# Varella_Aquisition_Module_-_v_2_0.net
KiCad netlist of a schematic drawn in EAGLE
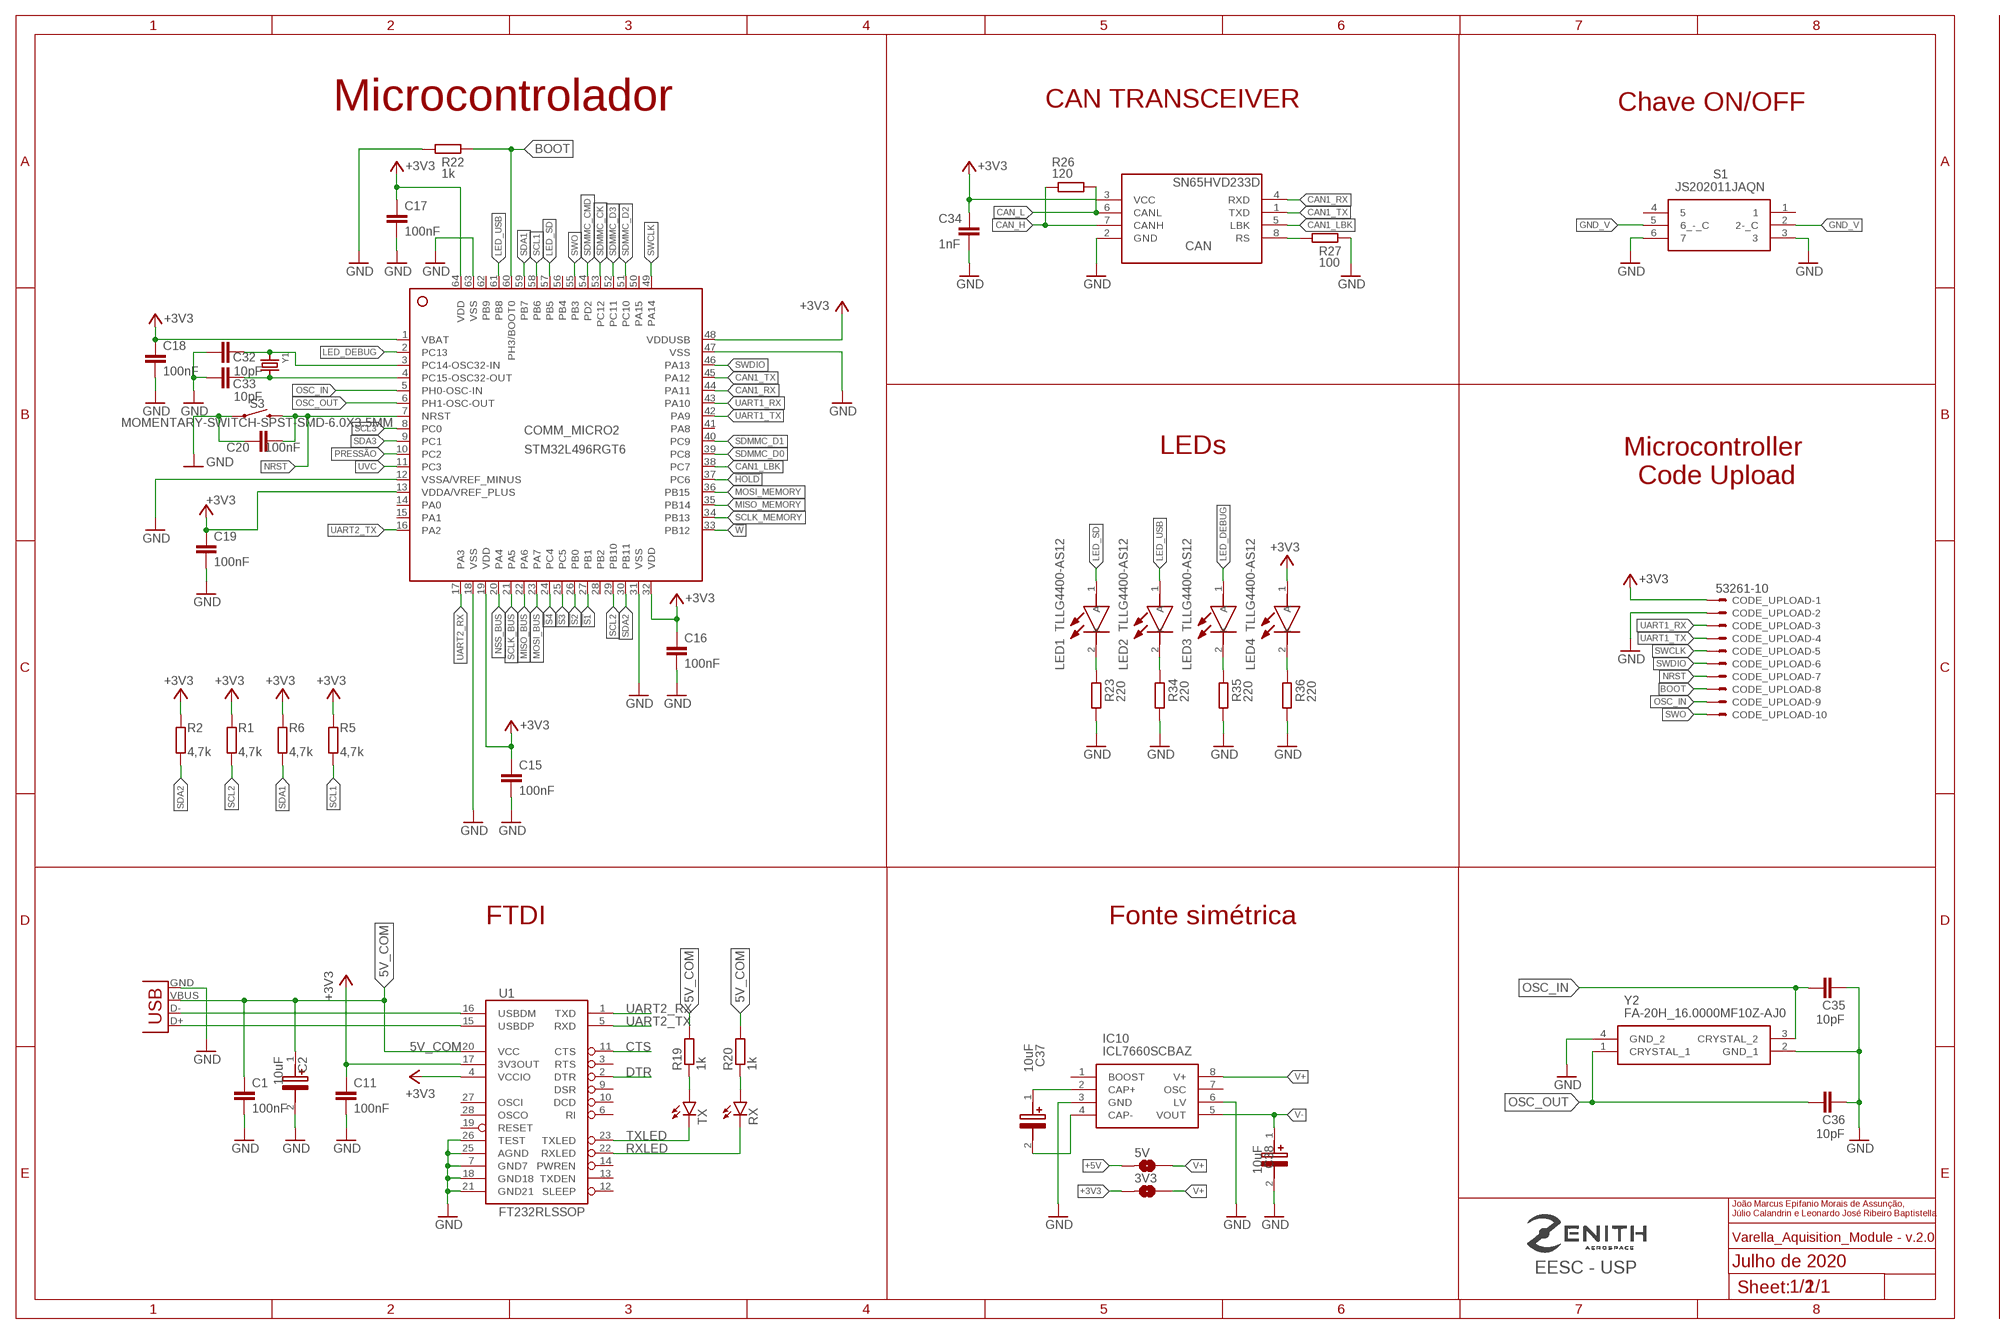
[diagram p0: schematic, sheet 1, part 1 of 2]
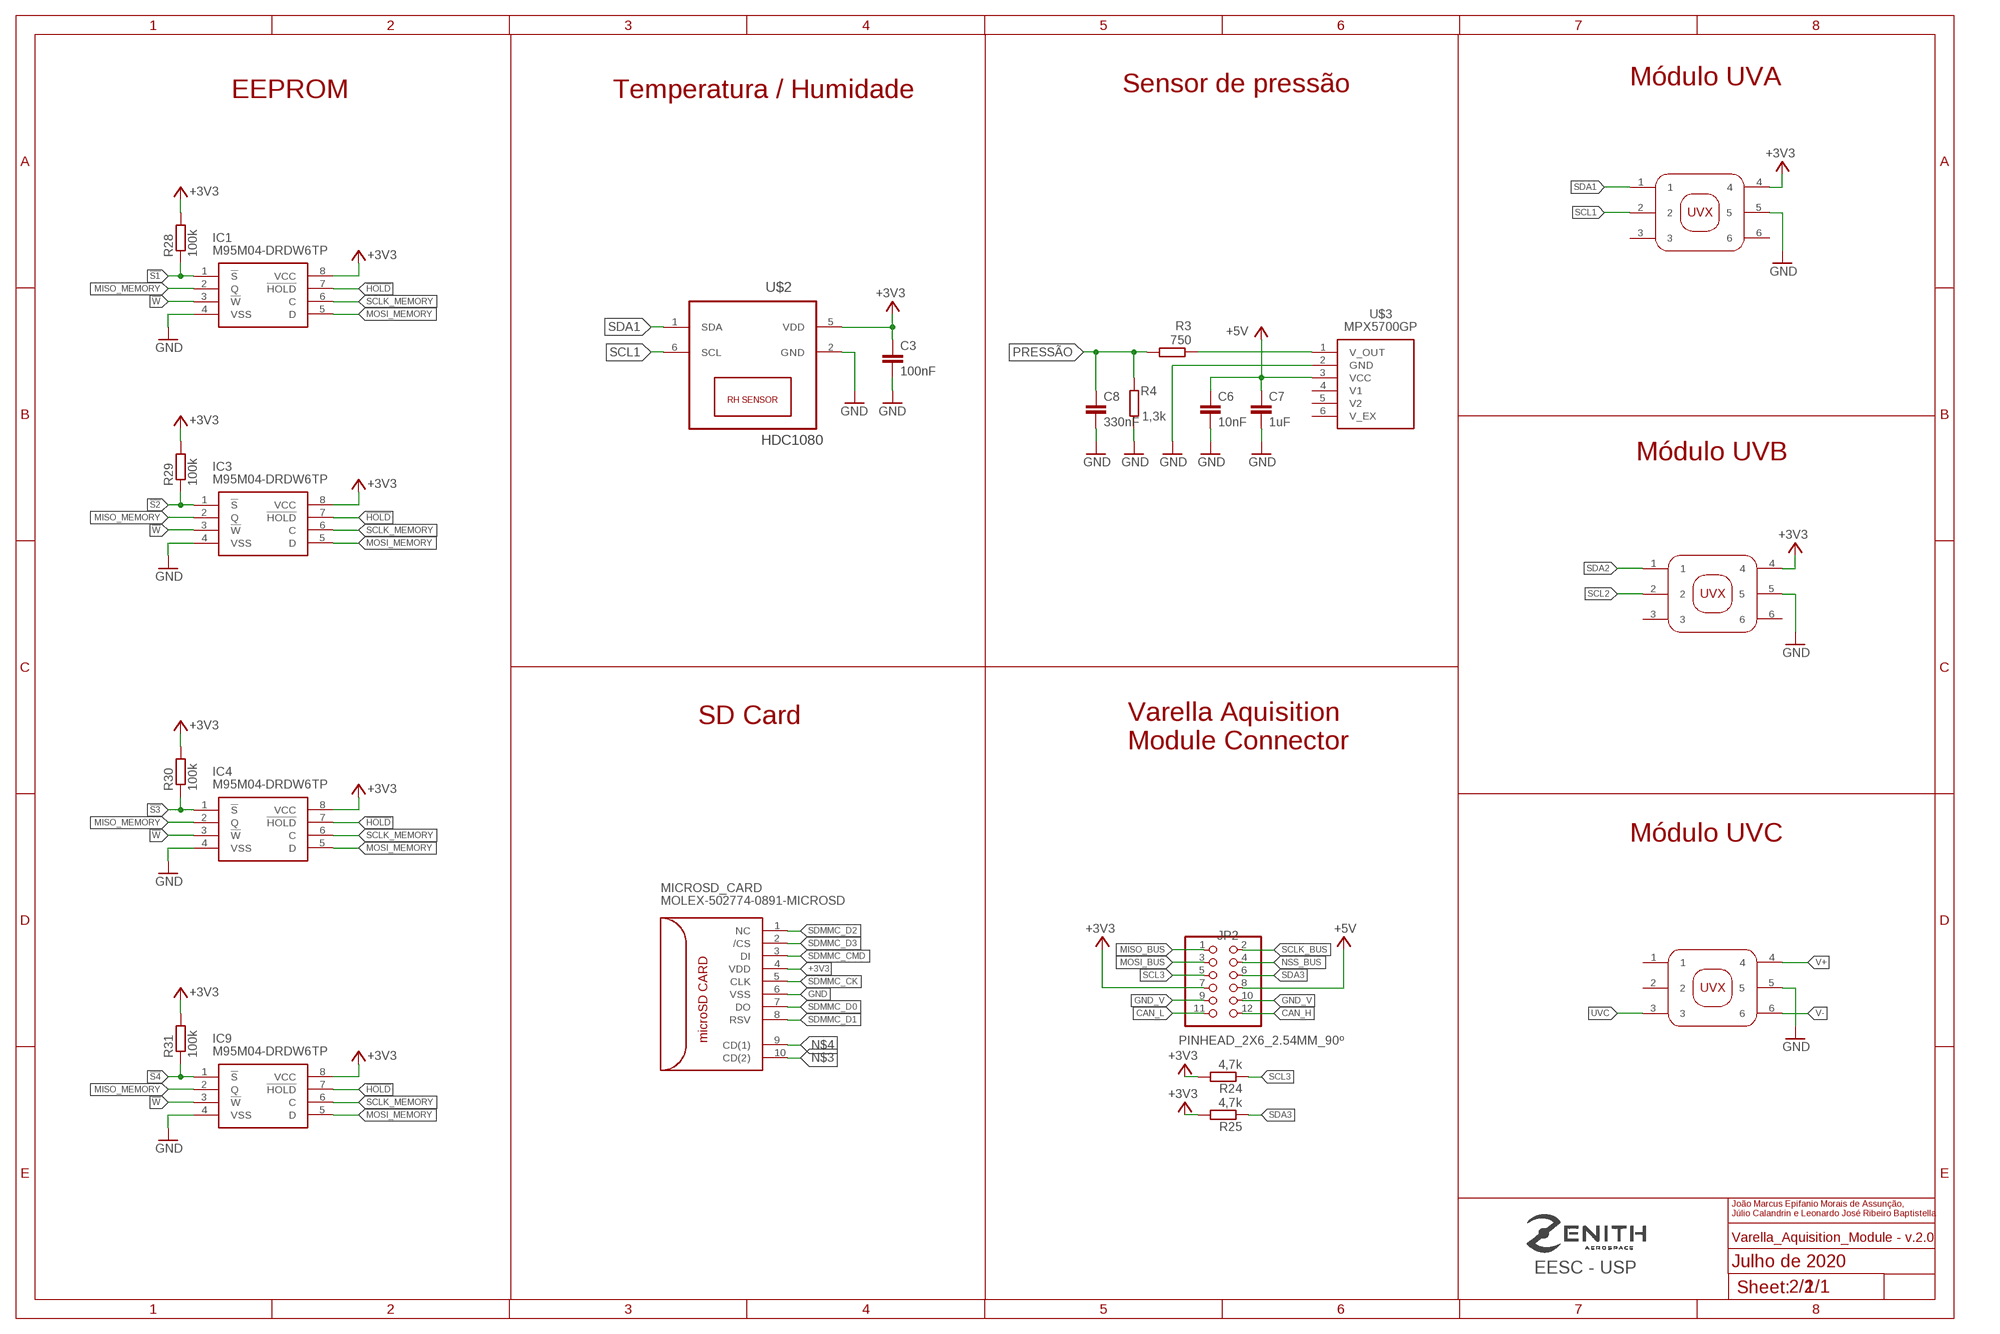
[diagram p1: schematic, sheet 1, part 2 of 2]

(export (version "E")
  (design (tool "Eeschema 10.0.6"))
  (components
    (comp (ref "3V3")
      (value "SMD-JUMPER-2")
      (footprint "eagle-import:SMD-JUMPER-2")
      (libsource (lib "eagle-import") (part "SMD-JUMPER-2"))
    )
    (comp (ref "5V")
      (value "SMD-JUMPER-2")
      (footprint "eagle-import:SMD-JUMPER-2")
      (libsource (lib "eagle-import") (part "SMD-JUMPER-2"))
    )
    (comp (ref "C1")
      (value "100nF")
      (footprint "eagle-import:C0805")
      (libsource (lib "eagle-import") (part "C-EUC0805"))
    )
    (comp (ref "C2")
      (value "10uF")
      (footprint "eagle-import:CAPAE430X610N")
      (fields
        (field (name "MANUFACTURER_PART_NUMBER") "EEE-FN1A100R")
        (field (name "MOUSER_PART_NUMBER") "667-EEE-FN1A100R")
      )
      (libsource (lib "eagle-import") (part "EEE-FN1A100R"))
    )
    (comp (ref "C3")
      (value "100nF")
      (footprint "eagle-import:C0805")
      (libsource (lib "eagle-import") (part "C-EUC0805"))
    )
    (comp (ref "C6")
      (value "10nF")
      (footprint "eagle-import:C0805")
      (libsource (lib "eagle-import") (part "C-EUC0805"))
    )
    (comp (ref "C7")
      (value "1uF")
      (footprint "eagle-import:C0805")
      (libsource (lib "eagle-import") (part "C-EUC0805"))
    )
    (comp (ref "C8")
      (value "330nF")
      (footprint "eagle-import:C0805")
      (libsource (lib "eagle-import") (part "C-EUC0805"))
    )
    (comp (ref "C11")
      (value "100nF")
      (footprint "eagle-import:C0805")
      (libsource (lib "eagle-import") (part "C-EUC0805"))
    )
    (comp (ref "C15")
      (value "100nF")
      (footprint "eagle-import:C0805")
      (libsource (lib "eagle-import") (part "C-EUC0805"))
    )
    (comp (ref "C16")
      (value "100nF")
      (footprint "eagle-import:C0805")
      (libsource (lib "eagle-import") (part "C-EUC0805"))
    )
    (comp (ref "C17")
      (value "100nF")
      (footprint "eagle-import:C0805")
      (libsource (lib "eagle-import") (part "C-EUC0805"))
    )
    (comp (ref "C18")
      (value "100nF")
      (footprint "eagle-import:C0805")
      (libsource (lib "eagle-import") (part "C-EUC0805"))
    )
    (comp (ref "C19")
      (value "100nF")
      (footprint "eagle-import:C0805")
      (libsource (lib "eagle-import") (part "C-EUC0805"))
    )
    (comp (ref "C20")
      (value "100nF")
      (footprint "eagle-import:C0805")
      (libsource (lib "eagle-import") (part "C-EUC0805"))
    )
    (comp (ref "C32")
      (value "10pF")
      (footprint "eagle-import:C0805")
      (libsource (lib "eagle-import") (part "C-EUC0805"))
    )
    (comp (ref "C33")
      (value "10pF")
      (footprint "eagle-import:C0805")
      (libsource (lib "eagle-import") (part "C-EUC0805"))
    )
    (comp (ref "C34")
      (value "1nF")
      (footprint "eagle-import:C1206")
      (libsource (lib "eagle-import") (part "C-EUC1206"))
    )
    (comp (ref "C35")
      (value "10pF")
      (footprint "eagle-import:C0805")
      (libsource (lib "eagle-import") (part "C-EUC0805"))
    )
    (comp (ref "C36")
      (value "10pF")
      (footprint "eagle-import:C0805")
      (libsource (lib "eagle-import") (part "C-EUC0805"))
    )
    (comp (ref "C37")
      (value "10uF")
      (footprint "eagle-import:CAPAE430X610N")
      (fields
        (field (name "MANUFACTURER_PART_NUMBER") "EEE-FN1A100R")
        (field (name "MOUSER_PART_NUMBER") "667-EEE-FN1A100R")
      )
      (libsource (lib "eagle-import") (part "EEE-FN1A100R"))
    )
    (comp (ref "C38")
      (value "10uF")
      (footprint "eagle-import:CAPAE430X610N")
      (fields
        (field (name "MANUFACTURER_PART_NUMBER") "EEE-FN1A100R")
        (field (name "MOUSER_PART_NUMBER") "667-EEE-FN1A100R")
      )
      (libsource (lib "eagle-import") (part "EEE-FN1A100R"))
    )
    (comp (ref "CAN")
      (value "SN65HVD233D")
      (footprint "eagle-import:SOIC8")
      (fields (field (name "MF") "Texas Instruments"))
      (libsource (lib "eagle-import") (part "SN65HVD233D"))
    )
    (comp (ref "CODE_UPLOAD")
      (value "53261-10")
      (footprint "eagle-import:53261-10")
      (fields (field (name "MF") "MOLEX"))
      (libsource (lib "eagle-import") (part "53?-10261"))
    )
    (comp (ref "COMM_MICRO2")
      (value "STM32L496RGT6")
      (footprint "eagle-import:LQFP64_10X10")
      (libsource (lib "eagle-import") (part "STM32L496RGT6"))
    )
    (comp (ref "IC1")
      (value "M95M04-DRDW6TP")
      (footprint "eagle-import:SOP65P640X120-8N")
      (fields (field (name "MOUSER_PART_NUMBER") "511-M95M04-DRDW6TP"))
      (libsource (lib "eagle-import") (part "M95M04-DRDW6TP"))
    )
    (comp (ref "IC3")
      (value "M95M04-DRDW6TP")
      (footprint "eagle-import:SOP65P640X120-8N")
      (fields (field (name "MOUSER_PART_NUMBER") "511-M95M04-DRDW6TP"))
      (libsource (lib "eagle-import") (part "M95M04-DRDW6TP"))
    )
    (comp (ref "IC4")
      (value "M95M04-DRDW6TP")
      (footprint "eagle-import:SOP65P640X120-8N")
      (fields (field (name "MOUSER_PART_NUMBER") "511-M95M04-DRDW6TP"))
      (libsource (lib "eagle-import") (part "M95M04-DRDW6TP"))
    )
    (comp (ref "IC9")
      (value "M95M04-DRDW6TP")
      (footprint "eagle-import:SOP65P640X120-8N")
      (fields (field (name "MOUSER_PART_NUMBER") "511-M95M04-DRDW6TP"))
      (libsource (lib "eagle-import") (part "M95M04-DRDW6TP"))
    )
    (comp (ref "IC10")
      (value "ICL7660SCBAZ")
      (footprint "eagle-import:SOIC127P600X175-8N@1")
      (fields (field (name "MOUSER_PART_NUMBER") "968-ICL7660SCBAZ"))
      (libsource (lib "eagle-import") (part "ICL7660SCBAZ"))
    )
    (comp (ref "JP2")
      (value "PINHEAD_2X6_2.54MM_90º")
      (footprint "eagle-import:PINHEAD_2X6_2.54MM_90º")
      (libsource (lib "eagle-import") (part "PINHEAD_2X6_2.54MM_90º"))
    )
    (comp (ref "LED1")
      (value "TLLG4400-AS12")
      (footprint "eagle-import:TLLG4400AS12")
      (fields (field (name "MOUSER_PART_NUMBER") "78-TLLG4400-AS12"))
      (libsource (lib "eagle-import") (part "TLLG4400-AS12"))
    )
    (comp (ref "LED2")
      (value "TLLG4400-AS12")
      (footprint "eagle-import:TLLG4400AS12")
      (fields (field (name "MOUSER_PART_NUMBER") "78-TLLG4400-AS12"))
      (libsource (lib "eagle-import") (part "TLLG4400-AS12"))
    )
    (comp (ref "LED3")
      (value "TLLG4400-AS12")
      (footprint "eagle-import:TLLG4400AS12")
      (fields (field (name "MOUSER_PART_NUMBER") "78-TLLG4400-AS12"))
      (libsource (lib "eagle-import") (part "TLLG4400-AS12"))
    )
    (comp (ref "LED4")
      (value "TLLG4400-AS12")
      (footprint "eagle-import:TLLG4400AS12")
      (fields (field (name "MOUSER_PART_NUMBER") "78-TLLG4400-AS12"))
      (libsource (lib "eagle-import") (part "TLLG4400-AS12"))
    )
    (comp (ref "MICROSD_CARD")
      (value "MOLEX-502774-0891-MICROSD")
      (footprint "eagle-import:MOLEX-502774-0891-MICROSD")
      (libsource (lib "eagle-import") (part "MOLEX-502774-0891-MICROSD"))
    )
    (comp (ref "R1")
      (value "4,7k")
      (footprint "eagle-import:R0805")
      (libsource (lib "eagle-import") (part "R-EU_R0805"))
    )
    (comp (ref "R2")
      (value "4,7k")
      (footprint "eagle-import:R0805")
      (libsource (lib "eagle-import") (part "R-EU_R0805"))
    )
    (comp (ref "R3")
      (value "750")
      (footprint "eagle-import:R0805")
      (libsource (lib "eagle-import") (part "R-EU_R0805"))
    )
    (comp (ref "R4")
      (value "1,3k")
      (footprint "eagle-import:R0805")
      (libsource (lib "eagle-import") (part "R-EU_R0805"))
    )
    (comp (ref "R5")
      (value "4,7k")
      (footprint "eagle-import:R0805")
      (libsource (lib "eagle-import") (part "R-EU_R0805"))
    )
    (comp (ref "R6")
      (value "4,7k")
      (footprint "eagle-import:R0805")
      (libsource (lib "eagle-import") (part "R-EU_R0805"))
    )
    (comp (ref "R19")
      (value "1k")
      (footprint "eagle-import:R0805")
      (libsource (lib "eagle-import") (part "R-EU_R0805"))
    )
    (comp (ref "R20")
      (value "1k")
      (footprint "eagle-import:R0805")
      (libsource (lib "eagle-import") (part "R-EU_R0805"))
    )
    (comp (ref "R22")
      (value "1k")
      (footprint "eagle-import:R0805")
      (libsource (lib "eagle-import") (part "R-EU_R0805"))
    )
    (comp (ref "R23")
      (value "220")
      (footprint "eagle-import:R0805")
      (libsource (lib "eagle-import") (part "R-EU_R0805"))
    )
    (comp (ref "R24")
      (value "4,7k")
      (footprint "eagle-import:R0805")
      (libsource (lib "eagle-import") (part "R-EU_R0805"))
    )
    (comp (ref "R25")
      (value "4,7k")
      (footprint "eagle-import:R0805")
      (libsource (lib "eagle-import") (part "R-EU_R0805"))
    )
    (comp (ref "R26")
      (value "120")
      (footprint "eagle-import:R1206")
      (libsource (lib "eagle-import") (part "R-EU_R1206"))
    )
    (comp (ref "R27")
      (value "100")
      (footprint "eagle-import:R0805")
      (libsource (lib "eagle-import") (part "R-EU_R0805"))
    )
    (comp (ref "R28")
      (value "100k")
      (footprint "eagle-import:R0805")
      (libsource (lib "eagle-import") (part "R-EU_R0805"))
    )
    (comp (ref "R29")
      (value "100k")
      (footprint "eagle-import:R0805")
      (libsource (lib "eagle-import") (part "R-EU_R0805"))
    )
    (comp (ref "R30")
      (value "100k")
      (footprint "eagle-import:R0805")
      (libsource (lib "eagle-import") (part "R-EU_R0805"))
    )
    (comp (ref "R31")
      (value "100k")
      (footprint "eagle-import:R0805")
      (libsource (lib "eagle-import") (part "R-EU_R0805"))
    )
    (comp (ref "R34")
      (value "220")
      (footprint "eagle-import:R0805")
      (libsource (lib "eagle-import") (part "R-EU_R0805"))
    )
    (comp (ref "R35")
      (value "220")
      (footprint "eagle-import:R0805")
      (libsource (lib "eagle-import") (part "R-EU_R0805"))
    )
    (comp (ref "R36")
      (value "220")
      (footprint "eagle-import:R0805")
      (libsource (lib "eagle-import") (part "R-EU_R0805"))
    )
    (comp (ref "RX")
      (value "LEDCHIPLED_0805")
      (footprint "eagle-import:CHIPLED_0805")
      (libsource (lib "eagle-import") (part "LEDCHIPLED_0805"))
    )
    (comp (ref "S1")
      (value "JS202011JAQN")
      (footprint "eagle-import:JS202011JAQN")
      (fields (field (name "MOUSER_PART_NUMBER") "611-JS202011JAQN"))
      (libsource (lib "eagle-import") (part "JS202011JAQN"))
    )
    (comp (ref "S3")
      (value "MOMENTARY-SWITCH-SPST-SMD-6.0X3.5MM")
      (footprint "eagle-import:TACTILE_SWITCH_SMD_6.0X3.5MM")
      (libsource (lib "eagle-import") (part "MOMENTARY-SWITCH-SPST-SMD-6.0X3.5MM"))
    )
    (comp (ref "TX")
      (value "LEDCHIPLED_0805")
      (footprint "eagle-import:CHIPLED_0805")
      (libsource (lib "eagle-import") (part "LEDCHIPLED_0805"))
    )
    (comp (ref "U$2")
      (value "HDC1080")
      (footprint "eagle-import:TI-S-PWSON-N6")
      (libsource (lib "eagle-import") (part "HDC1080"))
    )
    (comp (ref "U$3")
      (value "MPX5700GP")
      (footprint "eagle-import:MPX5700GP")
      (libsource (lib "eagle-import") (part "MPX5700GP"))
    )
    (comp (ref "U$6")
      (value "MODULO_UV")
      (footprint "eagle-import:MODULO_UV")
      (libsource (lib "eagle-import") (part "MODULO_UV"))
    )
    (comp (ref "U$7")
      (value "MODULO_UV")
      (footprint "eagle-import:MODULO_UV")
      (libsource (lib "eagle-import") (part "MODULO_UV"))
    )
    (comp (ref "U$8")
      (value "MODULO_UV")
      (footprint "eagle-import:MODULO_UV")
      (libsource (lib "eagle-import") (part "MODULO_UV"))
    )
    (comp (ref "U1")
      (value "FT232RLSSOP")
      (footprint "eagle-import:SSOP28DB")
      (libsource (lib "eagle-import") (part "FT232RLSSOP"))
    )
    (comp (ref "X2")
      (value "USB-SMD-NS")
      (footprint "eagle-import:USB-MINIB-NOSTOP")
      (libsource (lib "eagle-import") (part "USB-SMD-NS"))
    )
    (comp (ref "Y1")
      (value "CRYSTAL8X3.8SMT")
      (footprint "eagle-import:CRYSTAL_8X3.8")
      (libsource (lib "eagle-import") (part "CRYSTAL8X3.8SMT"))
    )
    (comp (ref "Y2")
      (value "FA-20H_16.0000MF10Z-AJ0")
      (footprint "eagle-import:FA20H160000MF12ZAC3")
      (fields
        (field (name "MANUFACTURER_PART_NUMBER") "FA-20H 16.0000MF10Z-AJ0")
        (field (name "MOUSER_PART_NUMBER") "732-FA-20H16MF10ZAJ0")
      )
      (libsource (lib "eagle-import") (part "FA-20H_16.0000MF10Z-AJ0"))
    )
  )
  (nets
    (net (code "1") (name "+3V3") (class "Default")
      (node (ref "3V3") (pin "2") (pinfunction "2_2") (pintype "passive"))
      (node (ref "C11") (pin "1") (pinfunction "1_1") (pintype "passive"))
      (node (ref "C15") (pin "1") (pinfunction "1_1") (pintype "passive"))
      (node (ref "C16") (pin "1") (pinfunction "1_1") (pintype "passive"))
      (node (ref "C17") (pin "1") (pinfunction "1_1") (pintype "passive"))
      (node (ref "C18") (pin "1") (pinfunction "1_1") (pintype "passive"))
      (node (ref "C19") (pin "1") (pinfunction "1_1") (pintype "passive"))
      (node (ref "C3") (pin "1") (pinfunction "1_1") (pintype "passive"))
      (node (ref "C34") (pin "1") (pinfunction "1_1") (pintype "passive"))
      (node (ref "CAN") (pin "3") (pinfunction "VCC_3") (pintype "power_in"))
      (node (ref "CODE_UPLOAD") (pin "1") (pinfunction "S_1") (pintype "passive"))
      (node (ref "COMM_MICRO2") (pin "1") (pinfunction "VBAT_1") (pintype "passive"))
      (node (ref "COMM_MICRO2") (pin "13") (pinfunction "VDDA/VREF_PLUS_13") (pintype "passive"))
      (node (ref "COMM_MICRO2") (pin "19") (pinfunction "VDD_19") (pintype "power_in"))
      (node (ref "COMM_MICRO2") (pin "32") (pinfunction "VDD_32") (pintype "power_in"))
      (node (ref "COMM_MICRO2") (pin "48") (pinfunction "VDDUSB_48") (pintype "bidirectional"))
      (node (ref "COMM_MICRO2") (pin "64") (pinfunction "VDD_64") (pintype "power_in"))
      (node (ref "IC1") (pin "8") (pinfunction "VCC_8") (pintype "bidirectional"))
      (node (ref "IC3") (pin "8") (pinfunction "VCC_8") (pintype "bidirectional"))
      (node (ref "IC4") (pin "8") (pinfunction "VCC_8") (pintype "bidirectional"))
      (node (ref "IC9") (pin "8") (pinfunction "VCC_8") (pintype "bidirectional"))
      (node (ref "JP2") (pin "7") (pinfunction "7_7") (pintype "passive"))
      (node (ref "LED4") (pin "1") (pinfunction "A_1") (pintype "bidirectional"))
      (node (ref "MICROSD_CARD") (pin "4") (pinfunction "VDD_4") (pintype "bidirectional"))
      (node (ref "R1") (pin "2") (pinfunction "2_2") (pintype "passive"))
      (node (ref "R2") (pin "2") (pinfunction "2_2") (pintype "passive"))
      (node (ref "R24") (pin "2") (pinfunction "2_2") (pintype "passive"))
      (node (ref "R25") (pin "2") (pinfunction "2_2") (pintype "passive"))
      (node (ref "R28") (pin "2") (pinfunction "2_2") (pintype "passive"))
      (node (ref "R29") (pin "2") (pinfunction "2_2") (pintype "passive"))
      (node (ref "R30") (pin "2") (pinfunction "2_2") (pintype "passive"))
      (node (ref "R31") (pin "2") (pinfunction "2_2") (pintype "passive"))
      (node (ref "R5") (pin "2") (pinfunction "2_2") (pintype "passive"))
      (node (ref "R6") (pin "2") (pinfunction "2_2") (pintype "passive"))
      (node (ref "U$2") (pin "5") (pinfunction "VDD_5") (pintype "output"))
      (node (ref "U$6") (pin "4") (pinfunction "4_4") (pintype "bidirectional"))
      (node (ref "U$7") (pin "4") (pinfunction "4_4") (pintype "bidirectional"))
      (node (ref "U1") (pin "17") (pinfunction "3V3OUT_17") (pintype "output"))
      (node (ref "U1") (pin "4") (pinfunction "VCCIO_4") (pintype "power_in"))
    )
    (net (code "2") (name "+5V") (class "Default")
      (node (ref "5V") (pin "2") (pinfunction "2_2") (pintype "passive"))
      (node (ref "C6") (pin "1") (pinfunction "1_1") (pintype "passive"))
      (node (ref "C7") (pin "1") (pinfunction "1_1") (pintype "passive"))
      (node (ref "JP2") (pin "8") (pinfunction "8_8") (pintype "passive"))
      (node (ref "U$3") (pin "3") (pinfunction "VCC_3") (pintype "bidirectional"))
    )
    (net (code "3") (name "/CTS") (class "Default")
      (node (ref "U1") (pin "11") (pinfunction "CTS_11") (pintype "input"))
    )
    (net (code "4") (name "/DTR") (class "Default")
      (node (ref "U1") (pin "2") (pinfunction "DTR_2") (pintype "output"))
    )
    (net (code "5") (name "/RXLED") (class "Default")
      (node (ref "RX") (pin "C") (pinfunction "C_C") (pintype "passive"))
      (node (ref "U1") (pin "22") (pinfunction "RXLED_22") (pintype "input"))
    )
    (net (code "6") (name "/TXLED") (class "Default")
      (node (ref "TX") (pin "C") (pinfunction "C_C") (pintype "passive"))
      (node (ref "U1") (pin "23") (pinfunction "TXLED_23") (pintype "input"))
    )
    (net (code "7") (name "/~{HOLD}") (class "Default")
      (node (ref "COMM_MICRO2") (pin "37") (pinfunction "PC6_37") (pintype "bidirectional"))
      (node (ref "IC1") (pin "7") (pinfunction "~{HOLD}_7") (pintype "bidirectional"))
      (node (ref "IC3") (pin "7") (pinfunction "~{HOLD}_7") (pintype "bidirectional"))
      (node (ref "IC4") (pin "7") (pinfunction "~{HOLD}_7") (pintype "bidirectional"))
      (node (ref "IC9") (pin "7") (pinfunction "~{HOLD}_7") (pintype "bidirectional"))
    )
    (net (code "8") (name "/~{S1}") (class "Default")
      (node (ref "COMM_MICRO2") (pin "27") (pinfunction "PB1_27") (pintype "bidirectional"))
      (node (ref "IC1") (pin "1") (pinfunction "~{S}_1") (pintype "bidirectional"))
      (node (ref "R28") (pin "1") (pinfunction "1_1") (pintype "passive"))
    )
    (net (code "9") (name "/~{S2}") (class "Default")
      (node (ref "COMM_MICRO2") (pin "26") (pinfunction "PB0_26") (pintype "bidirectional"))
      (node (ref "IC3") (pin "1") (pinfunction "~{S}_1") (pintype "bidirectional"))
      (node (ref "R29") (pin "1") (pinfunction "1_1") (pintype "passive"))
    )
    (net (code "10") (name "/~{S3}") (class "Default")
      (node (ref "COMM_MICRO2") (pin "25") (pinfunction "PC5_25") (pintype "bidirectional"))
      (node (ref "IC4") (pin "1") (pinfunction "~{S}_1") (pintype "bidirectional"))
      (node (ref "R30") (pin "1") (pinfunction "1_1") (pintype "passive"))
    )
    (net (code "11") (name "/~{S4}") (class "Default")
      (node (ref "COMM_MICRO2") (pin "24") (pinfunction "PC4_24") (pintype "bidirectional"))
      (node (ref "IC9") (pin "1") (pinfunction "~{S}_1") (pintype "bidirectional"))
      (node (ref "R31") (pin "1") (pinfunction "1_1") (pintype "passive"))
    )
    (net (code "12") (name "/~{W}") (class "Default")
      (node (ref "COMM_MICRO2") (pin "33") (pinfunction "PB12_33") (pintype "bidirectional"))
      (node (ref "IC1") (pin "3") (pinfunction "~{W}_3") (pintype "bidirectional"))
      (node (ref "IC3") (pin "3") (pinfunction "~{W}_3") (pintype "bidirectional"))
      (node (ref "IC4") (pin "3") (pinfunction "~{W}_3") (pintype "bidirectional"))
      (node (ref "IC9") (pin "3") (pinfunction "~{W}_3") (pintype "bidirectional"))
    )
    (net (code "13") (name "5V_COM") (class "Default")
      (node (ref "C1") (pin "1") (pinfunction "1_1") (pintype "passive"))
      (node (ref "C2") (pin "1") (pinfunction "+_1") (pintype "bidirectional"))
      (node (ref "R19") (pin "2") (pinfunction "2_2") (pintype "passive"))
      (node (ref "R20") (pin "2") (pinfunction "2_2") (pintype "passive"))
      (node (ref "U1") (pin "20") (pinfunction "VCC_20") (pintype "power_in"))
      (node (ref "X2") (pin "VBUS") (pinfunction "VBUS_VBUS") (pintype "bidirectional"))
    )
    (net (code "14") (name "BOOT") (class "Default")
      (node (ref "CODE_UPLOAD") (pin "8") (pinfunction "S_8") (pintype "passive"))
      (node (ref "COMM_MICRO2") (pin "60") (pinfunction "PH3/BOOT0_60") (pintype "input"))
      (node (ref "R22") (pin "1") (pinfunction "1_1") (pintype "passive"))
    )
    (net (code "15") (name "CAN1_LBK") (class "Default")
      (node (ref "CAN") (pin "5") (pinfunction "LBK_5") (pintype "output"))
      (node (ref "COMM_MICRO2") (pin "38") (pinfunction "PC7_38") (pintype "bidirectional"))
    )
    (net (code "16") (name "CAN1_RX") (class "Default")
      (node (ref "CAN") (pin "4") (pinfunction "RXD_4") (pintype "output"))
      (node (ref "COMM_MICRO2") (pin "44") (pinfunction "PA11_44") (pintype "bidirectional"))
    )
    (net (code "17") (name "CAN1_TX") (class "Default")
      (node (ref "CAN") (pin "1") (pinfunction "TXD_1") (pintype "bidirectional"))
      (node (ref "COMM_MICRO2") (pin "45") (pinfunction "PA12_45") (pintype "bidirectional"))
    )
    (net (code "18") (name "CAN_H") (class "Default")
      (node (ref "CAN") (pin "7") (pinfunction "CANH_7") (pintype "bidirectional"))
      (node (ref "JP2") (pin "12") (pinfunction "12_12") (pintype "passive"))
      (node (ref "R26") (pin "1") (pinfunction "1_1") (pintype "passive"))
    )
    (net (code "19") (name "CAN_L") (class "Default")
      (node (ref "CAN") (pin "6") (pinfunction "CANL_6") (pintype "bidirectional"))
      (node (ref "JP2") (pin "11") (pinfunction "11_11") (pintype "passive"))
      (node (ref "R26") (pin "2") (pinfunction "2_2") (pintype "passive"))
    )
    (net (code "20") (name "GND") (class "Default")
      (node (ref "C1") (pin "2") (pinfunction "2_2") (pintype "passive"))
      (node (ref "C11") (pin "2") (pinfunction "2_2") (pintype "passive"))
      (node (ref "C15") (pin "2") (pinfunction "2_2") (pintype "passive"))
      (node (ref "C16") (pin "2") (pinfunction "2_2") (pintype "passive"))
      (node (ref "C17") (pin "2") (pinfunction "2_2") (pintype "passive"))
      (node (ref "C18") (pin "2") (pinfunction "2_2") (pintype "passive"))
      (node (ref "C19") (pin "2") (pinfunction "2_2") (pintype "passive"))
      (node (ref "C2") (pin "2") (pinfunction "-_2") (pintype "bidirectional"))
      (node (ref "C20") (pin "1") (pinfunction "1_1") (pintype "passive"))
      (node (ref "C3") (pin "2") (pinfunction "2_2") (pintype "passive"))
      (node (ref "C32") (pin "1") (pinfunction "1_1") (pintype "passive"))
      (node (ref "C33") (pin "1") (pinfunction "1_1") (pintype "passive"))
      (node (ref "C34") (pin "2") (pinfunction "2_2") (pintype "passive"))
      (node (ref "C35") (pin "2") (pinfunction "2_2") (pintype "passive"))
      (node (ref "C36") (pin "2") (pinfunction "2_2") (pintype "passive"))
      (node (ref "C38") (pin "2") (pinfunction "-_2") (pintype "bidirectional"))
      (node (ref "C6") (pin "2") (pinfunction "2_2") (pintype "passive"))
      (node (ref "C7") (pin "2") (pinfunction "2_2") (pintype "passive"))
      (node (ref "C8") (pin "2") (pinfunction "2_2") (pintype "passive"))
      (node (ref "CAN") (pin "2") (pinfunction "GND_2") (pintype "power_in"))
      (node (ref "CODE_UPLOAD") (pin "2") (pinfunction "S_2") (pintype "passive"))
      (node (ref "COMM_MICRO2") (pin "12") (pinfunction "VSSA/VREF_MINUS_12") (pintype "passive"))
      (node (ref "COMM_MICRO2") (pin "18") (pinfunction "VSS_18") (pintype "power_in"))
      (node (ref "COMM_MICRO2") (pin "31") (pinfunction "VSS_31") (pintype "power_in"))
      (node (ref "COMM_MICRO2") (pin "47") (pinfunction "VSS_47") (pintype "power_in"))
      (node (ref "COMM_MICRO2") (pin "63") (pinfunction "VSS_63") (pintype "power_in"))
      (node (ref "IC1") (pin "4") (pinfunction "VSS_4") (pintype "bidirectional"))
      (node (ref "IC10") (pin "3") (pinfunction "GND_3") (pintype "bidirectional"))
      (node (ref "IC10") (pin "6") (pinfunction "LV_6") (pintype "bidirectional"))
      (node (ref "IC3") (pin "4") (pinfunction "VSS_4") (pintype "bidirectional"))
      (node (ref "IC4") (pin "4") (pinfunction "VSS_4") (pintype "bidirectional"))
      (node (ref "IC9") (pin "4") (pinfunction "VSS_4") (pintype "bidirectional"))
      (node (ref "MICROSD_CARD") (pin "6") (pinfunction "VSS_6") (pintype "bidirectional"))
      (node (ref "R22") (pin "2") (pinfunction "2_2") (pintype "passive"))
      (node (ref "R23") (pin "1") (pinfunction "1_1") (pintype "passive"))
      (node (ref "R27") (pin "1") (pinfunction "1_1") (pintype "passive"))
      (node (ref "R34") (pin "1") (pinfunction "1_1") (pintype "passive"))
      (node (ref "R35") (pin "1") (pinfunction "1_1") (pintype "passive"))
      (node (ref "R36") (pin "1") (pinfunction "1_1") (pintype "passive"))
      (node (ref "R4") (pin "2") (pinfunction "2_2") (pintype "passive"))
      (node (ref "S1") (pin "3") (pinfunction "3_3") (pintype "bidirectional"))
      (node (ref "S1") (pin "6") (pinfunction "7_6") (pintype "bidirectional"))
      (node (ref "S3") (pin "1") (pinfunction "1_1") (pintype "passive"))
      (node (ref "U$2") (pin "2") (pinfunction "GND_2") (pintype "passive"))
      (node (ref "U$6") (pin "5") (pinfunction "5_5") (pintype "bidirectional"))
      (node (ref "U$7") (pin "5") (pinfunction "5_5") (pintype "bidirectional"))
      (node (ref "U$8") (pin "5") (pinfunction "5_5") (pintype "bidirectional"))
      (node (ref "U1") (pin "18") (pinfunction "GND18_18") (pintype "power_in"))
      (node (ref "U1") (pin "21") (pinfunction "GND21_21") (pintype "power_in"))
      (node (ref "U1") (pin "25") (pinfunction "AGND_25") (pintype "power_in"))
      (node (ref "U1") (pin "26") (pinfunction "TEST_26") (pintype "input"))
      (node (ref "U1") (pin "7") (pinfunction "GND7_7") (pintype "power_in"))
      (node (ref "X2") (pin "GND") (pinfunction "GND_GND") (pintype "bidirectional"))
      (node (ref "Y2") (pin "2") (pinfunction "GND_1_2") (pintype "bidirectional"))
      (node (ref "Y2") (pin "4") (pinfunction "GND_2_4") (pintype "bidirectional"))
    )
    (net (code "21") (name "GND_V") (class "Default")
      (node (ref "JP2") (pin "10") (pinfunction "10_10") (pintype "passive"))
      (node (ref "JP2") (pin "9") (pinfunction "9_9") (pintype "passive"))
      (node (ref "S1") (pin "2") (pinfunction "2-_C_2") (pintype "bidirectional"))
      (node (ref "S1") (pin "5") (pinfunction "6_-_C_5") (pintype "bidirectional"))
    )
    (net (code "22") (name "LED_DEBUG") (class "Default")
      (node (ref "COMM_MICRO2") (pin "2") (pinfunction "PC13_2") (pintype "bidirectional"))
      (node (ref "LED3") (pin "1") (pinfunction "A_1") (pintype "bidirectional"))
    )
    (net (code "23") (name "LED_SD") (class "Default")
      (node (ref "COMM_MICRO2") (pin "57") (pinfunction "PB5_57") (pintype "bidirectional"))
      (node (ref "LED1") (pin "1") (pinfunction "A_1") (pintype "bidirectional"))
    )
    (net (code "24") (name "LED_USB") (class "Default")
      (node (ref "COMM_MICRO2") (pin "61") (pinfunction "PB8_61") (pintype "bidirectional"))
      (node (ref "LED2") (pin "1") (pinfunction "A_1") (pintype "bidirectional"))
    )
    (net (code "25") (name "MISO_BUS") (class "Default")
      (node (ref "COMM_MICRO2") (pin "22") (pinfunction "PA6_22") (pintype "bidirectional"))
      (node (ref "JP2") (pin "1") (pinfunction "1_1") (pintype "passive"))
    )
    (net (code "26") (name "MISO_MEMORY") (class "Default")
      (node (ref "COMM_MICRO2") (pin "35") (pinfunction "PB14_35") (pintype "bidirectional"))
      (node (ref "IC1") (pin "2") (pinfunction "Q_2") (pintype "bidirectional"))
      (node (ref "IC3") (pin "2") (pinfunction "Q_2") (pintype "bidirectional"))
      (node (ref "IC4") (pin "2") (pinfunction "Q_2") (pintype "bidirectional"))
      (node (ref "IC9") (pin "2") (pinfunction "Q_2") (pintype "bidirectional"))
    )
    (net (code "27") (name "MOSI_BUS") (class "Default")
      (node (ref "COMM_MICRO2") (pin "23") (pinfunction "PA7_23") (pintype "bidirectional"))
      (node (ref "JP2") (pin "3") (pinfunction "3_3") (pintype "passive"))
    )
    (net (code "28") (name "MOSI_MEMORY") (class "Default")
      (node (ref "COMM_MICRO2") (pin "36") (pinfunction "PB15_36") (pintype "bidirectional"))
      (node (ref "IC1") (pin "5") (pinfunction "D_5") (pintype "bidirectional"))
      (node (ref "IC3") (pin "5") (pinfunction "D_5") (pintype "bidirectional"))
      (node (ref "IC4") (pin "5") (pinfunction "D_5") (pintype "bidirectional"))
      (node (ref "IC9") (pin "5") (pinfunction "D_5") (pintype "bidirectional"))
    )
    (net (code "29") (name "N$3") (class "Default")
      (node (ref "MICROSD_CARD") (pin "10") (pinfunction "CD(2)_10") (pintype "bidirectional"))
    )
    (net (code "30") (name "N$4") (class "Default")
      (node (ref "MICROSD_CARD") (pin "9") (pinfunction "CD(1)_9") (pintype "bidirectional"))
    )
    (net (code "31") (name "NRST") (class "Default")
      (node (ref "C20") (pin "2") (pinfunction "2_2") (pintype "passive"))
      (node (ref "CODE_UPLOAD") (pin "7") (pinfunction "S_7") (pintype "passive"))
      (node (ref "COMM_MICRO2") (pin "7") (pinfunction "NRST_7") (pintype "input"))
      (node (ref "S3") (pin "2") (pinfunction "2_2") (pintype "passive"))
    )
    (net (code "32") (name "NSS_BUS") (class "Default")
      (node (ref "COMM_MICRO2") (pin "20") (pinfunction "PA4_20") (pintype "bidirectional"))
      (node (ref "JP2") (pin "4") (pinfunction "4_4") (pintype "passive"))
    )
    (net (code "33") (name "Net-(C37-+)") (class "Default")
      (node (ref "C37") (pin "1") (pinfunction "+_1") (pintype "bidirectional"))
      (node (ref "IC10") (pin "2") (pinfunction "CAP+_2") (pintype "bidirectional"))
    )
    (net (code "34") (name "Net-(C37--)") (class "Default")
      (node (ref "C37") (pin "2") (pinfunction "-_2") (pintype "bidirectional"))
      (node (ref "IC10") (pin "4") (pinfunction "CAP-_4") (pintype "bidirectional"))
    )
    (net (code "35") (name "Net-(CAN-RS)") (class "Default")
      (node (ref "CAN") (pin "8") (pinfunction "RS_8") (pintype "input"))
      (node (ref "R27") (pin "2") (pinfunction "2_2") (pintype "passive"))
    )
    (net (code "36") (name "Net-(COMM_MICRO2-PC14-OSC32-IN)") (class "Default")
      (node (ref "C32") (pin "2") (pinfunction "2_2") (pintype "passive"))
      (node (ref "COMM_MICRO2") (pin "3") (pinfunction "PC14-OSC32-IN_3") (pintype "bidirectional"))
      (node (ref "Y1") (pin "P$1") (pinfunction "1_P$1") (pintype "passive"))
    )
    (net (code "37") (name "Net-(COMM_MICRO2-PC15-OSC32-OUT)") (class "Default")
      (node (ref "C33") (pin "2") (pinfunction "2_2") (pintype "passive"))
      (node (ref "COMM_MICRO2") (pin "4") (pinfunction "PC15-OSC32-OUT_4") (pintype "bidirectional"))
      (node (ref "Y1") (pin "P$4") (pinfunction "2_P$4") (pintype "passive"))
    )
    (net (code "38") (name "Net-(LED1-K)") (class "Default")
      (node (ref "LED1") (pin "2") (pinfunction "K_2") (pintype "bidirectional"))
      (node (ref "R23") (pin "2") (pinfunction "2_2") (pintype "passive"))
    )
    (net (code "39") (name "Net-(LED2-K)") (class "Default")
      (node (ref "LED2") (pin "2") (pinfunction "K_2") (pintype "bidirectional"))
      (node (ref "R34") (pin "2") (pinfunction "2_2") (pintype "passive"))
    )
    (net (code "40") (name "Net-(LED3-K)") (class "Default")
      (node (ref "LED3") (pin "2") (pinfunction "K_2") (pintype "bidirectional"))
      (node (ref "R35") (pin "2") (pinfunction "2_2") (pintype "passive"))
    )
    (net (code "41") (name "Net-(LED4-K)") (class "Default")
      (node (ref "LED4") (pin "2") (pinfunction "K_2") (pintype "bidirectional"))
      (node (ref "R36") (pin "2") (pinfunction "2_2") (pintype "passive"))
    )
    (net (code "42") (name "Net-(R19-Pad1)") (class "Default")
      (node (ref "R19") (pin "1") (pinfunction "1_1") (pintype "passive"))
      (node (ref "TX") (pin "A") (pinfunction "A_A") (pintype "passive"))
    )
    (net (code "43") (name "Net-(R20-Pad1)") (class "Default")
      (node (ref "R20") (pin "1") (pinfunction "1_1") (pintype "passive"))
      (node (ref "RX") (pin "A") (pinfunction "A_A") (pintype "passive"))
    )
    (net (code "44") (name "Net-(U$3-V_OUT)") (class "Default")
      (node (ref "R3") (pin "1") (pinfunction "1_1") (pintype "passive"))
      (node (ref "U$3") (pin "1") (pinfunction "V_OUT_1") (pintype "bidirectional"))
    )
    (net (code "45") (name "Net-(U1-USBDM)") (class "Default")
      (node (ref "U1") (pin "16") (pinfunction "USBDM_16") (pintype "bidirectional"))
      (node (ref "X2") (pin "D-") (pinfunction "D-_D-") (pintype "bidirectional"))
    )
    (net (code "46") (name "Net-(U1-USBDP)") (class "Default")
      (node (ref "U1") (pin "15") (pinfunction "USBDP_15") (pintype "bidirectional"))
      (node (ref "X2") (pin "D+") (pinfunction "D+_D+") (pintype "bidirectional"))
    )
    (net (code "47") (name "OSC_IN") (class "Default")
      (node (ref "C35") (pin "1") (pinfunction "1_1") (pintype "passive"))
      (node (ref "CODE_UPLOAD") (pin "9") (pinfunction "S_9") (pintype "passive"))
      (node (ref "COMM_MICRO2") (pin "5") (pinfunction "PH0-OSC-IN_5") (pintype "bidirectional"))
      (node (ref "Y2") (pin "3") (pinfunction "CRYSTAL_2_3") (pintype "bidirectional"))
    )
    (net (code "48") (name "OSC_OUT") (class "Default")
      (node (ref "C36") (pin "1") (pinfunction "1_1") (pintype "passive"))
      (node (ref "COMM_MICRO2") (pin "6") (pinfunction "PH1-OSC-OUT_6") (pintype "bidirectional"))
      (node (ref "Y2") (pin "1") (pinfunction "CRYSTAL_1_1") (pintype "bidirectional"))
    )
    (net (code "49") (name "PRESSÃO") (class "Default")
      (node (ref "C8") (pin "1") (pinfunction "1_1") (pintype "passive"))
      (node (ref "COMM_MICRO2") (pin "10") (pinfunction "PC2_10") (pintype "bidirectional"))
      (node (ref "R3") (pin "2") (pinfunction "2_2") (pintype "passive"))
      (node (ref "R4") (pin "1") (pinfunction "1_1") (pintype "passive"))
    )
    (net (code "50") (name "SCL1") (class "Default")
      (node (ref "COMM_MICRO2") (pin "58") (pinfunction "PB6_58") (pintype "bidirectional"))
      (node (ref "R5") (pin "1") (pinfunction "1_1") (pintype "passive"))
      (node (ref "U$2") (pin "6") (pinfunction "SCL_6") (pintype "passive"))
      (node (ref "U$6") (pin "2") (pinfunction "2_2") (pintype "bidirectional"))
    )
    (net (code "51") (name "SCL2") (class "Default")
      (node (ref "COMM_MICRO2") (pin "29") (pinfunction "PB10_29") (pintype "bidirectional"))
      (node (ref "R1") (pin "1") (pinfunction "1_1") (pintype "passive"))
      (node (ref "U$7") (pin "2") (pinfunction "2_2") (pintype "bidirectional"))
    )
    (net (code "52") (name "SCL3") (class "Default")
      (node (ref "COMM_MICRO2") (pin "8") (pinfunction "PC0_8") (pintype "bidirectional"))
      (node (ref "JP2") (pin "5") (pinfunction "5_5") (pintype "passive"))
      (node (ref "R24") (pin "1") (pinfunction "1_1") (pintype "passive"))
    )
    (net (code "53") (name "SCLK_BUS") (class "Default")
      (node (ref "COMM_MICRO2") (pin "21") (pinfunction "PA5_21") (pintype "bidirectional"))
      (node (ref "JP2") (pin "2") (pinfunction "2_2") (pintype "passive"))
    )
    (net (code "54") (name "SCLK_MEMORY") (class "Default")
      (node (ref "COMM_MICRO2") (pin "34") (pinfunction "PB13_34") (pintype "bidirectional"))
      (node (ref "IC1") (pin "6") (pinfunction "C_6") (pintype "bidirectional"))
      (node (ref "IC3") (pin "6") (pinfunction "C_6") (pintype "bidirectional"))
      (node (ref "IC4") (pin "6") (pinfunction "C_6") (pintype "bidirectional"))
      (node (ref "IC9") (pin "6") (pinfunction "C_6") (pintype "bidirectional"))
    )
    (net (code "55") (name "SDA1") (class "Default")
      (node (ref "COMM_MICRO2") (pin "59") (pinfunction "PB7_59") (pintype "bidirectional"))
      (node (ref "R6") (pin "1") (pinfunction "1_1") (pintype "passive"))
      (node (ref "U$2") (pin "1") (pinfunction "SDA_1") (pintype "power_in"))
      (node (ref "U$6") (pin "1") (pinfunction "1_1") (pintype "bidirectional"))
    )
    (net (code "56") (name "SDA2") (class "Default")
      (node (ref "COMM_MICRO2") (pin "30") (pinfunction "PB11_30") (pintype "bidirectional"))
      (node (ref "R2") (pin "1") (pinfunction "1_1") (pintype "passive"))
      (node (ref "U$7") (pin "1") (pinfunction "1_1") (pintype "bidirectional"))
    )
    (net (code "57") (name "SDA3") (class "Default")
      (node (ref "COMM_MICRO2") (pin "9") (pinfunction "PC1_9") (pintype "bidirectional"))
      (node (ref "JP2") (pin "6") (pinfunction "6_6") (pintype "passive"))
      (node (ref "R25") (pin "1") (pinfunction "1_1") (pintype "passive"))
    )
    (net (code "58") (name "SDMMC_CK") (class "Default")
      (node (ref "COMM_MICRO2") (pin "53") (pinfunction "PC12_53") (pintype "bidirectional"))
      (node (ref "MICROSD_CARD") (pin "5") (pinfunction "CLK_5") (pintype "bidirectional"))
    )
    (net (code "59") (name "SDMMC_CMD") (class "Default")
      (node (ref "COMM_MICRO2") (pin "54") (pinfunction "PD2_54") (pintype "bidirectional"))
      (node (ref "MICROSD_CARD") (pin "3") (pinfunction "DI_3") (pintype "bidirectional"))
    )
    (net (code "60") (name "SDMMC_D0") (class "Default")
      (node (ref "COMM_MICRO2") (pin "39") (pinfunction "PC8_39") (pintype "bidirectional"))
      (node (ref "MICROSD_CARD") (pin "7") (pinfunction "DO_7") (pintype "bidirectional"))
    )
    (net (code "61") (name "SDMMC_D1") (class "Default")
      (node (ref "COMM_MICRO2") (pin "40") (pinfunction "PC9_40") (pintype "bidirectional"))
      (node (ref "MICROSD_CARD") (pin "8") (pinfunction "RSV_8") (pintype "bidirectional"))
    )
    (net (code "62") (name "SDMMC_D2") (class "Default")
      (node (ref "COMM_MICRO2") (pin "51") (pinfunction "PC10_51") (pintype "bidirectional"))
      (node (ref "MICROSD_CARD") (pin "1") (pinfunction "NC_1") (pintype "bidirectional"))
    )
    (net (code "63") (name "SDMMC_D3") (class "Default")
      (node (ref "COMM_MICRO2") (pin "52") (pinfunction "PC11_52") (pintype "bidirectional"))
      (node (ref "MICROSD_CARD") (pin "2") (pinfunction "/CS_2") (pintype "bidirectional"))
    )
    (net (code "64") (name "SWCLK") (class "Default")
      (node (ref "CODE_UPLOAD") (pin "5") (pinfunction "S_5") (pintype "passive"))
      (node (ref "COMM_MICRO2") (pin "49") (pinfunction "PA14_49") (pintype "input"))
    )
    (net (code "65") (name "SWDIO") (class "Default")
      (node (ref "CODE_UPLOAD") (pin "6") (pinfunction "S_6") (pintype "passive"))
      (node (ref "COMM_MICRO2") (pin "46") (pinfunction "PA13_46") (pintype "input"))
    )
    (net (code "66") (name "SWO") (class "Default")
      (node (ref "CODE_UPLOAD") (pin "10") (pinfunction "S_10") (pintype "passive"))
      (node (ref "COMM_MICRO2") (pin "55") (pinfunction "PB3_55") (pintype "output"))
    )
    (net (code "67") (name "UART1_RX") (class "Default")
      (node (ref "CODE_UPLOAD") (pin "3") (pinfunction "S_3") (pintype "passive"))
      (node (ref "COMM_MICRO2") (pin "43") (pinfunction "PA10_43") (pintype "bidirectional"))
    )
    (net (code "68") (name "UART1_TX") (class "Default")
      (node (ref "CODE_UPLOAD") (pin "4") (pinfunction "S_4") (pintype "passive"))
      (node (ref "COMM_MICRO2") (pin "42") (pinfunction "PA9_42") (pintype "bidirectional"))
    )
    (net (code "69") (name "UART2_RX") (class "Default")
      (node (ref "COMM_MICRO2") (pin "17") (pinfunction "PA3_17") (pintype "bidirectional"))
      (node (ref "U1") (pin "1") (pinfunction "TXD_1") (pintype "output"))
    )
    (net (code "70") (name "UART2_TX") (class "Default")
      (node (ref "COMM_MICRO2") (pin "16") (pinfunction "PA2_16") (pintype "bidirectional"))
      (node (ref "U1") (pin "5") (pinfunction "RXD_5") (pintype "input"))
    )
    (net (code "71") (name "UVC") (class "Default")
      (node (ref "COMM_MICRO2") (pin "11") (pinfunction "PC3_11") (pintype "bidirectional"))
      (node (ref "U$8") (pin "3") (pinfunction "3_3") (pintype "bidirectional"))
    )
    (net (code "72") (name "V+") (class "Default")
      (node (ref "3V3") (pin "1") (pinfunction "1_1") (pintype "passive"))
      (node (ref "5V") (pin "1") (pinfunction "1_1") (pintype "passive"))
      (node (ref "IC10") (pin "8") (pinfunction "V+_8") (pintype "bidirectional"))
      (node (ref "U$8") (pin "4") (pinfunction "4_4") (pintype "bidirectional"))
    )
    (net (code "73") (name "V-") (class "Default")
      (node (ref "C38") (pin "1") (pinfunction "+_1") (pintype "bidirectional"))
      (node (ref "IC10") (pin "5") (pinfunction "VOUT_5") (pintype "bidirectional"))
      (node (ref "U$8") (pin "6") (pinfunction "6_6") (pintype "bidirectional"))
    )
    (net (code "74") (name "unconnected-(COMM_MICRO2-PA0-Pad14)") (class "Default")
      (node (ref "COMM_MICRO2") (pin "14") (pinfunction "PA0_14") (pintype "bidirectional"))
    )
    (net (code "75") (name "unconnected-(COMM_MICRO2-PA1-Pad15)") (class "Default")
      (node (ref "COMM_MICRO2") (pin "15") (pinfunction "PA1_15") (pintype "bidirectional"))
    )
    (net (code "76") (name "unconnected-(COMM_MICRO2-PA8-Pad41)") (class "Default")
      (node (ref "COMM_MICRO2") (pin "41") (pinfunction "PA8_41") (pintype "bidirectional"))
    )
    (net (code "77") (name "unconnected-(COMM_MICRO2-PA15-Pad50)") (class "Default")
      (node (ref "COMM_MICRO2") (pin "50") (pinfunction "PA15_50") (pintype "input"))
    )
    (net (code "78") (name "unconnected-(COMM_MICRO2-PB2-Pad28)") (class "Default")
      (node (ref "COMM_MICRO2") (pin "28") (pinfunction "PB2_28") (pintype "bidirectional"))
    )
    (net (code "79") (name "unconnected-(COMM_MICRO2-PB4-Pad56)") (class "Default")
      (node (ref "COMM_MICRO2") (pin "56") (pinfunction "PB4_56") (pintype "input"))
    )
    (net (code "80") (name "unconnected-(COMM_MICRO2-PB9-Pad62)") (class "Default")
      (node (ref "COMM_MICRO2") (pin "62") (pinfunction "PB9_62") (pintype "bidirectional"))
    )
    (net (code "81") (name "unconnected-(IC10-BOOST-Pad1)") (class "Default")
      (node (ref "IC10") (pin "1") (pinfunction "BOOST_1") (pintype "bidirectional"))
    )
    (net (code "82") (name "unconnected-(IC10-OSC-Pad7)") (class "Default")
      (node (ref "IC10") (pin "7") (pinfunction "OSC_7") (pintype "bidirectional"))
    )
    (net (code "83") (name "unconnected-(S1-5-Pad4)") (class "Default")
      (node (ref "S1") (pin "4") (pinfunction "5_4") (pintype "bidirectional"))
    )
    (net (code "84") (name "unconnected-(S1-Pad1)") (class "Default")
      (node (ref "S1") (pin "1") (pinfunction "1_1") (pintype "bidirectional"))
    )
    (net (code "85") (name "unconnected-(U$3-GND-Pad2)") (class "Default")
      (node (ref "U$3") (pin "2") (pinfunction "GND_2") (pintype "bidirectional"))
    )
    (net (code "86") (name "unconnected-(U$3-V1-Pad4)") (class "Default")
      (node (ref "U$3") (pin "4") (pinfunction "V1_4") (pintype "bidirectional"))
    )
    (net (code "87") (name "unconnected-(U$3-V2-Pad5)") (class "Default")
      (node (ref "U$3") (pin "5") (pinfunction "V2_5") (pintype "bidirectional"))
    )
    (net (code "88") (name "unconnected-(U$3-V_EX-Pad6)") (class "Default")
      (node (ref "U$3") (pin "6") (pinfunction "V_EX_6") (pintype "bidirectional"))
    )
    (net (code "89") (name "unconnected-(U$6-Pad3)") (class "Default")
      (node (ref "U$6") (pin "3") (pinfunction "3_3") (pintype "bidirectional"))
    )
    (net (code "90") (name "unconnected-(U$6-Pad6)") (class "Default")
      (node (ref "U$6") (pin "6") (pinfunction "6_6") (pintype "bidirectional"))
    )
    (net (code "91") (name "unconnected-(U$7-Pad3)") (class "Default")
      (node (ref "U$7") (pin "3") (pinfunction "3_3") (pintype "bidirectional"))
    )
    (net (code "92") (name "unconnected-(U$7-Pad6)") (class "Default")
      (node (ref "U$7") (pin "6") (pinfunction "6_6") (pintype "bidirectional"))
    )
    (net (code "93") (name "unconnected-(U$8-Pad1)") (class "Default")
      (node (ref "U$8") (pin "1") (pinfunction "1_1") (pintype "bidirectional"))
    )
    (net (code "94") (name "unconnected-(U$8-Pad2)") (class "Default")
      (node (ref "U$8") (pin "2") (pinfunction "2_2") (pintype "bidirectional"))
    )
    (net (code "95") (name "unconnected-(U1-DCD-Pad10)") (class "Default")
      (node (ref "U1") (pin "10") (pinfunction "DCD_10") (pintype "input"))
    )
    (net (code "96") (name "unconnected-(U1-DSR-Pad9)") (class "Default")
      (node (ref "U1") (pin "9") (pinfunction "DSR_9") (pintype "input"))
    )
    (net (code "97") (name "unconnected-(U1-OSCI-Pad27)") (class "Default")
      (node (ref "U1") (pin "27") (pinfunction "OSCI_27") (pintype "input"))
    )
    (net (code "98") (name "unconnected-(U1-OSCO-Pad28)") (class "Default")
      (node (ref "U1") (pin "28") (pinfunction "OSCO_28") (pintype "output"))
    )
    (net (code "99") (name "unconnected-(U1-PWREN-Pad14)") (class "Default")
      (node (ref "U1") (pin "14") (pinfunction "PWREN_14") (pintype "input"))
    )
    (net (code "100") (name "unconnected-(U1-RESET-Pad19)") (class "Default")
      (node (ref "U1") (pin "19") (pinfunction "RESET_19") (pintype "input"))
    )
    (net (code "101") (name "unconnected-(U1-RI-Pad6)") (class "Default")
      (node (ref "U1") (pin "6") (pinfunction "RI_6") (pintype "input"))
    )
    (net (code "102") (name "unconnected-(U1-RTS-Pad3)") (class "Default")
      (node (ref "U1") (pin "3") (pinfunction "RTS_3") (pintype "output"))
    )
    (net (code "103") (name "unconnected-(U1-SLEEP-Pad12)") (class "Default")
      (node (ref "U1") (pin "12") (pinfunction "SLEEP_12") (pintype "input"))
    )
    (net (code "104") (name "unconnected-(U1-TXDEN-Pad13)") (class "Default")
      (node (ref "U1") (pin "13") (pinfunction "TXDEN_13") (pintype "input"))
    )
  )
)
